# relayboard.net
KiCad netlist of a schematic drawn in EAGLE
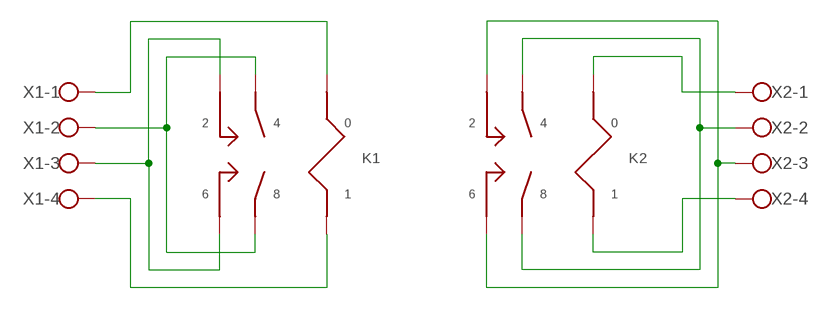
[diagram p0: schematic, sheet 1]

(export (version "E")
  (design (tool "Eeschema 10.0.6"))
  (components
    (comp (ref "K1")
      (value "T92S7D12-24")
      (footprint "eagle-import:T92")
      (libsource (lib "eagle-import") (part "T92S7D12-24"))
    )
    (comp (ref "K2")
      (value "T92S7D12-24")
      (footprint "eagle-import:T92")
      (libsource (lib "eagle-import") (part "T92S7D12-24"))
    )
    (comp (ref "X1")
      (value "W237-4")
      (footprint "eagle-import:W237-4")
      (libsource (lib "eagle-import") (part "W237-4"))
    )
    (comp (ref "X2")
      (value "W237-4")
      (footprint "eagle-import:W237-4")
      (libsource (lib "eagle-import") (part "W237-4"))
    )
  )
  (nets
    (net (code "1") (name "Net-(X1A-KL)") (class "Default")
      (node (ref "K1") (pin "P$10") (pinfunction "P$3_P$10") (pintype "bidirectional"))
      (node (ref "K1") (pin "P$9") (pinfunction "P$3_P$9") (pintype "bidirectional"))
      (node (ref "X1") (pin "1") (pinfunction "KL_1") (pintype "passive"))
    )
    (net (code "2") (name "Net-(X1B-KL)") (class "Default")
      (node (ref "K1") (pin "P$3") (pinfunction "P$2_P$3") (pintype "bidirectional"))
      (node (ref "K1") (pin "P$4") (pinfunction "P$2_P$4") (pintype "bidirectional"))
      (node (ref "K1") (pin "P$7") (pinfunction "P$5_P$7") (pintype "bidirectional"))
      (node (ref "K1") (pin "P$8") (pinfunction "P$5_P$8") (pintype "bidirectional"))
      (node (ref "X1") (pin "2") (pinfunction "KL_2") (pintype "passive"))
    )
    (net (code "3") (name "Net-(X1C-KL)") (class "Default")
      (node (ref "K1") (pin "P$1") (pinfunction "P$1_P$1") (pintype "bidirectional"))
      (node (ref "K1") (pin "P$2") (pinfunction "P$1_P$2") (pintype "bidirectional"))
      (node (ref "K1") (pin "P$5") (pinfunction "P$4_P$5") (pintype "bidirectional"))
      (node (ref "K1") (pin "P$6") (pinfunction "P$4_P$6") (pintype "bidirectional"))
      (node (ref "X1") (pin "3") (pinfunction "KL_3") (pintype "passive"))
    )
    (net (code "4") (name "Net-(X1D-KL)") (class "Default")
      (node (ref "K1") (pin "P$11") (pinfunction "P$6_P$11") (pintype "bidirectional"))
      (node (ref "K1") (pin "P$12") (pinfunction "P$6_P$12") (pintype "bidirectional"))
      (node (ref "X1") (pin "4") (pinfunction "KL_4") (pintype "passive"))
    )
    (net (code "5") (name "Net-(X2A-KL)") (class "Default")
      (node (ref "K2") (pin "P$10") (pinfunction "P$3_P$10") (pintype "bidirectional"))
      (node (ref "K2") (pin "P$9") (pinfunction "P$3_P$9") (pintype "bidirectional"))
      (node (ref "X2") (pin "1") (pinfunction "KL_1") (pintype "passive"))
    )
    (net (code "6") (name "Net-(X2B-KL)") (class "Default")
      (node (ref "K2") (pin "P$3") (pinfunction "P$2_P$3") (pintype "bidirectional"))
      (node (ref "K2") (pin "P$4") (pinfunction "P$2_P$4") (pintype "bidirectional"))
      (node (ref "K2") (pin "P$7") (pinfunction "P$5_P$7") (pintype "bidirectional"))
      (node (ref "K2") (pin "P$8") (pinfunction "P$5_P$8") (pintype "bidirectional"))
      (node (ref "X2") (pin "2") (pinfunction "KL_2") (pintype "passive"))
    )
    (net (code "7") (name "Net-(X2C-KL)") (class "Default")
      (node (ref "K2") (pin "P$1") (pinfunction "P$1_P$1") (pintype "bidirectional"))
      (node (ref "K2") (pin "P$2") (pinfunction "P$1_P$2") (pintype "bidirectional"))
      (node (ref "K2") (pin "P$5") (pinfunction "P$4_P$5") (pintype "bidirectional"))
      (node (ref "K2") (pin "P$6") (pinfunction "P$4_P$6") (pintype "bidirectional"))
      (node (ref "X2") (pin "3") (pinfunction "KL_3") (pintype "passive"))
    )
    (net (code "8") (name "Net-(X2D-KL)") (class "Default")
      (node (ref "K2") (pin "P$11") (pinfunction "P$6_P$11") (pintype "bidirectional"))
      (node (ref "K2") (pin "P$12") (pinfunction "P$6_P$12") (pintype "bidirectional"))
      (node (ref "X2") (pin "4") (pinfunction "KL_4") (pintype "passive"))
    )
  )
)
